# epiano.net
KiCad netlist of a schematic drawn in EAGLE
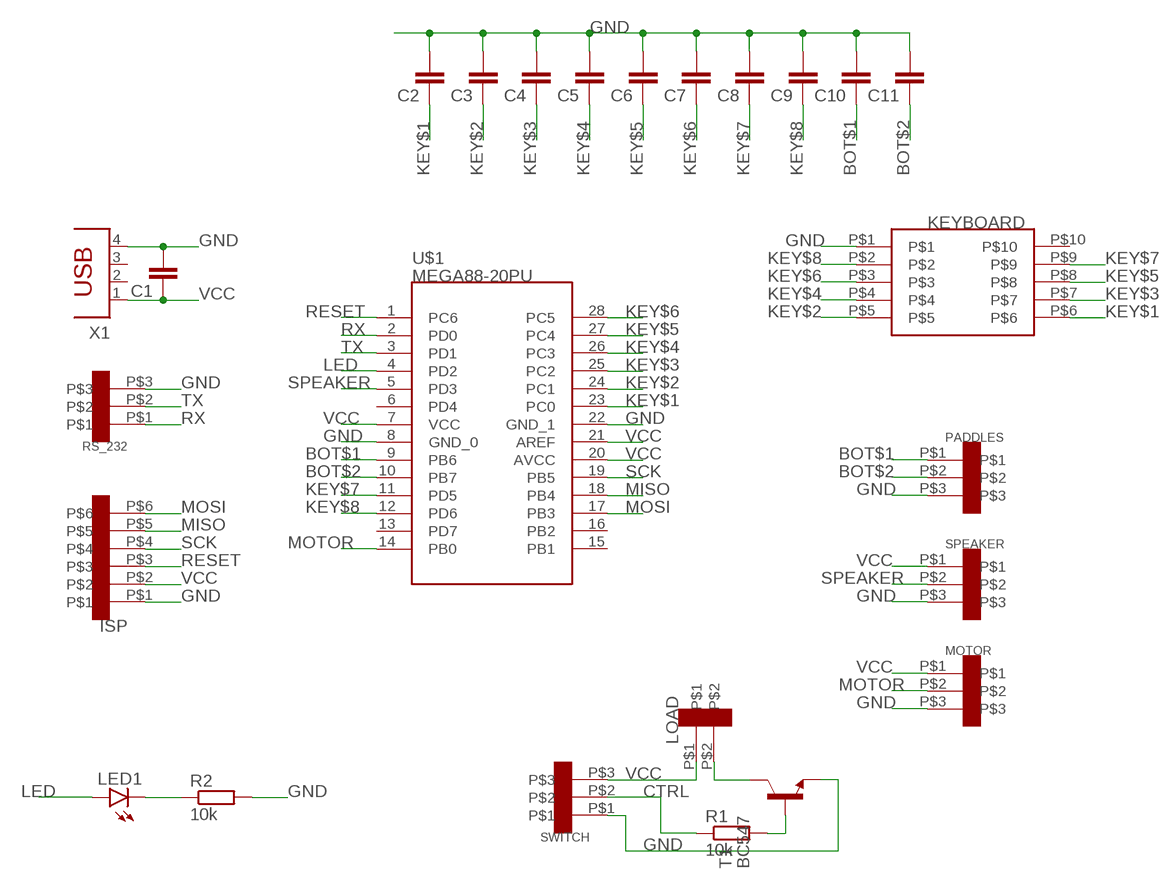
[diagram p0: schematic, sheet 1]

(export (version "E")
  (design (tool "Eeschema 10.0.6"))
  (components
    (comp (ref "C1")
      (value "C-EU025-060X050")
      (footprint "eagle-import:C025-060X050")
      (libsource (lib "eagle-import") (part "C-EU025-060X050"))
    )
    (comp (ref "C2")
      (value "C-EU025-024X044")
      (footprint "eagle-import:C025-024X044")
      (libsource (lib "eagle-import") (part "C-EU025-024X044"))
    )
    (comp (ref "C3")
      (value "C-EU025-024X044")
      (footprint "eagle-import:C025-024X044")
      (libsource (lib "eagle-import") (part "C-EU025-024X044"))
    )
    (comp (ref "C4")
      (value "C-EU025-024X044")
      (footprint "eagle-import:C025-024X044")
      (libsource (lib "eagle-import") (part "C-EU025-024X044"))
    )
    (comp (ref "C5")
      (value "C-EU025-024X044")
      (footprint "eagle-import:C025-024X044")
      (libsource (lib "eagle-import") (part "C-EU025-024X044"))
    )
    (comp (ref "C6")
      (value "C-EU025-024X044")
      (footprint "eagle-import:C025-024X044")
      (libsource (lib "eagle-import") (part "C-EU025-024X044"))
    )
    (comp (ref "C7")
      (value "C-EU025-024X044")
      (footprint "eagle-import:C025-024X044")
      (libsource (lib "eagle-import") (part "C-EU025-024X044"))
    )
    (comp (ref "C8")
      (value "C-EU025-024X044")
      (footprint "eagle-import:C025-024X044")
      (libsource (lib "eagle-import") (part "C-EU025-024X044"))
    )
    (comp (ref "C9")
      (value "C-EU025-024X044")
      (footprint "eagle-import:C025-024X044")
      (libsource (lib "eagle-import") (part "C-EU025-024X044"))
    )
    (comp (ref "C10")
      (value "C-EU025-024X044")
      (footprint "eagle-import:C025-024X044")
      (libsource (lib "eagle-import") (part "C-EU025-024X044"))
    )
    (comp (ref "C11")
      (value "C-EU025-024X044")
      (footprint "eagle-import:C025-024X044")
      (libsource (lib "eagle-import") (part "C-EU025-024X044"))
    )
    (comp (ref "ISP")
      (value "CON_DIL_6")
      (footprint "eagle-import:CON_DIL_6")
      (libsource (lib "eagle-import") (part "CON_DIL_6"))
    )
    (comp (ref "KEYBOARD")
      (value "CON_DIL_2X5")
      (footprint "eagle-import:CON_DIL_2X5")
      (libsource (lib "eagle-import") (part "CON_DIL_2X5"))
    )
    (comp (ref "LED1")
      (value "LED3MM")
      (footprint "eagle-import:LED3MM")
      (libsource (lib "eagle-import") (part "LED3MM"))
    )
    (comp (ref "LOAD")
      (value "CON_DIL_2")
      (footprint "eagle-import:CON_DIL_2")
      (libsource (lib "eagle-import") (part "CON_DIL_2"))
    )
    (comp (ref "MOTOR")
      (value "CON_DIL_3")
      (footprint "eagle-import:CON_DIL_3")
      (libsource (lib "eagle-import") (part "CON_DIL_3"))
    )
    (comp (ref "PADDLES")
      (value "CON_DIL_3")
      (footprint "eagle-import:CON_DIL_3")
      (libsource (lib "eagle-import") (part "CON_DIL_3"))
    )
    (comp (ref "R1")
      (value "10k")
      (footprint "eagle-import:0204_5")
      (libsource (lib "eagle-import") (part "R-EU_0204/5"))
    )
    (comp (ref "R2")
      (value "10k")
      (footprint "eagle-import:0207_15")
      (libsource (lib "eagle-import") (part "R-EU_0207/15"))
    )
    (comp (ref "RS_232")
      (value "CON_DIL_3")
      (footprint "eagle-import:CON_DIL_3")
      (libsource (lib "eagle-import") (part "CON_DIL_3"))
    )
    (comp (ref "SPEAKER")
      (value "CON_DIL_3")
      (footprint "eagle-import:CON_DIL_3")
      (libsource (lib "eagle-import") (part "CON_DIL_3"))
    )
    (comp (ref "SWITCH")
      (value "CON_DIL_3")
      (footprint "eagle-import:CON_DIL_3")
      (libsource (lib "eagle-import") (part "CON_DIL_3"))
    )
    (comp (ref "T1")
      (value "BC547")
      (footprint "eagle-import:TO92")
      (libsource (lib "eagle-import") (part "BC547"))
    )
    (comp (ref "U$1")
      (value "MEGA88-20PU")
      (footprint "eagle-import:DIL28-3")
      (libsource (lib "eagle-import") (part "MEGA88-20PU"))
    )
    (comp (ref "X1")
      (value "PN87520")
      (footprint "eagle-import:PN87520")
      (libsource (lib "eagle-import") (part "PN87520"))
    )
  )
  (nets
    (net (code "1") (name "/BOT$1") (class "Default")
      (node (ref "C10") (pin "1") (pinfunction "1_1") (pintype "passive"))
      (node (ref "PADDLES") (pin "P$1") (pinfunction "P$1_P$1") (pintype "bidirectional"))
      (node (ref "U$1") (pin "9") (pinfunction "PB6_9") (pintype "bidirectional"))
    )
    (net (code "2") (name "/BOT$2") (class "Default")
      (node (ref "C11") (pin "1") (pinfunction "1_1") (pintype "passive"))
      (node (ref "PADDLES") (pin "P$2") (pinfunction "P$2_P$2") (pintype "bidirectional"))
      (node (ref "U$1") (pin "10") (pinfunction "PB7_10") (pintype "bidirectional"))
    )
    (net (code "3") (name "/CTRL") (class "Default")
      (node (ref "R1") (pin "1") (pinfunction "1_1") (pintype "passive"))
      (node (ref "SWITCH") (pin "P$2") (pinfunction "P$2_P$2") (pintype "bidirectional"))
    )
    (net (code "4") (name "/GND") (class "Default")
      (node (ref "C1") (pin "2") (pinfunction "2_2") (pintype "passive"))
      (node (ref "C10") (pin "2") (pinfunction "2_2") (pintype "passive"))
      (node (ref "C11") (pin "2") (pinfunction "2_2") (pintype "passive"))
      (node (ref "C2") (pin "2") (pinfunction "2_2") (pintype "passive"))
      (node (ref "C3") (pin "2") (pinfunction "2_2") (pintype "passive"))
      (node (ref "C4") (pin "2") (pinfunction "2_2") (pintype "passive"))
      (node (ref "C5") (pin "2") (pinfunction "2_2") (pintype "passive"))
      (node (ref "C6") (pin "2") (pinfunction "2_2") (pintype "passive"))
      (node (ref "C7") (pin "2") (pinfunction "2_2") (pintype "passive"))
      (node (ref "C8") (pin "2") (pinfunction "2_2") (pintype "passive"))
      (node (ref "C9") (pin "2") (pinfunction "2_2") (pintype "passive"))
      (node (ref "ISP") (pin "P$1") (pinfunction "P$1_P$1") (pintype "bidirectional"))
      (node (ref "KEYBOARD") (pin "P$1") (pinfunction "P$1_P$1") (pintype "bidirectional"))
      (node (ref "MOTOR") (pin "P$3") (pinfunction "P$3_P$3") (pintype "bidirectional"))
      (node (ref "PADDLES") (pin "P$3") (pinfunction "P$3_P$3") (pintype "bidirectional"))
      (node (ref "R2") (pin "2") (pinfunction "2_2") (pintype "passive"))
      (node (ref "RS_232") (pin "P$3") (pinfunction "P$3_P$3") (pintype "bidirectional"))
      (node (ref "SPEAKER") (pin "P$3") (pinfunction "P$3_P$3") (pintype "bidirectional"))
      (node (ref "SWITCH") (pin "P$1") (pinfunction "P$1_P$1") (pintype "bidirectional"))
      (node (ref "T1") (pin "1") (pinfunction "E_1") (pintype "passive"))
      (node (ref "U$1") (pin "22") (pinfunction "GND_1_22") (pintype "bidirectional"))
      (node (ref "U$1") (pin "8") (pinfunction "GND_0_8") (pintype "bidirectional"))
      (node (ref "X1") (pin "4") (pinfunction "4_4") (pintype "passive"))
    )
    (net (code "5") (name "/KEY$1") (class "Default")
      (node (ref "C2") (pin "1") (pinfunction "1_1") (pintype "passive"))
      (node (ref "KEYBOARD") (pin "P$6") (pinfunction "P$6_P$6") (pintype "bidirectional"))
      (node (ref "U$1") (pin "23") (pinfunction "PC0_23") (pintype "bidirectional"))
    )
    (net (code "6") (name "/KEY$2") (class "Default")
      (node (ref "C3") (pin "1") (pinfunction "1_1") (pintype "passive"))
      (node (ref "KEYBOARD") (pin "P$5") (pinfunction "P$5_P$5") (pintype "bidirectional"))
      (node (ref "U$1") (pin "24") (pinfunction "PC1_24") (pintype "bidirectional"))
    )
    (net (code "7") (name "/KEY$3") (class "Default")
      (node (ref "C4") (pin "1") (pinfunction "1_1") (pintype "passive"))
      (node (ref "KEYBOARD") (pin "P$7") (pinfunction "P$7_P$7") (pintype "bidirectional"))
      (node (ref "U$1") (pin "25") (pinfunction "PC2_25") (pintype "bidirectional"))
    )
    (net (code "8") (name "/KEY$4") (class "Default")
      (node (ref "C5") (pin "1") (pinfunction "1_1") (pintype "passive"))
      (node (ref "KEYBOARD") (pin "P$4") (pinfunction "P$4_P$4") (pintype "bidirectional"))
      (node (ref "U$1") (pin "26") (pinfunction "PC3_26") (pintype "bidirectional"))
    )
    (net (code "9") (name "/KEY$5") (class "Default")
      (node (ref "C6") (pin "1") (pinfunction "1_1") (pintype "passive"))
      (node (ref "KEYBOARD") (pin "P$8") (pinfunction "P$8_P$8") (pintype "bidirectional"))
      (node (ref "U$1") (pin "27") (pinfunction "PC4_27") (pintype "bidirectional"))
    )
    (net (code "10") (name "/KEY$6") (class "Default")
      (node (ref "C7") (pin "1") (pinfunction "1_1") (pintype "passive"))
      (node (ref "KEYBOARD") (pin "P$3") (pinfunction "P$3_P$3") (pintype "bidirectional"))
      (node (ref "U$1") (pin "28") (pinfunction "PC5_28") (pintype "bidirectional"))
    )
    (net (code "11") (name "/KEY$7") (class "Default")
      (node (ref "C8") (pin "1") (pinfunction "1_1") (pintype "passive"))
      (node (ref "KEYBOARD") (pin "P$9") (pinfunction "P$9_P$9") (pintype "bidirectional"))
      (node (ref "U$1") (pin "11") (pinfunction "PD5_11") (pintype "bidirectional"))
    )
    (net (code "12") (name "/KEY$8") (class "Default")
      (node (ref "C9") (pin "1") (pinfunction "1_1") (pintype "passive"))
      (node (ref "KEYBOARD") (pin "P$2") (pinfunction "P$2_P$2") (pintype "bidirectional"))
      (node (ref "U$1") (pin "12") (pinfunction "PD6_12") (pintype "bidirectional"))
    )
    (net (code "13") (name "/LED") (class "Default")
      (node (ref "LED1") (pin "A") (pinfunction "A_A") (pintype "passive"))
      (node (ref "U$1") (pin "4") (pinfunction "PD2_4") (pintype "bidirectional"))
    )
    (net (code "14") (name "/MISO") (class "Default")
      (node (ref "ISP") (pin "P$5") (pinfunction "P$5_P$5") (pintype "bidirectional"))
      (node (ref "U$1") (pin "18") (pinfunction "PB4_18") (pintype "bidirectional"))
    )
    (net (code "15") (name "/MOSI") (class "Default")
      (node (ref "ISP") (pin "P$6") (pinfunction "P$6_P$6") (pintype "bidirectional"))
      (node (ref "U$1") (pin "17") (pinfunction "PB3_17") (pintype "bidirectional"))
    )
    (net (code "16") (name "/MOTOR") (class "Default")
      (node (ref "MOTOR") (pin "P$2") (pinfunction "P$2_P$2") (pintype "bidirectional"))
      (node (ref "U$1") (pin "14") (pinfunction "PB0_14") (pintype "bidirectional"))
    )
    (net (code "17") (name "/RESET") (class "Default")
      (node (ref "ISP") (pin "P$3") (pinfunction "P$3_P$3") (pintype "bidirectional"))
      (node (ref "U$1") (pin "1") (pinfunction "PC6_1") (pintype "bidirectional"))
    )
    (net (code "18") (name "/RX") (class "Default")
      (node (ref "RS_232") (pin "P$1") (pinfunction "P$1_P$1") (pintype "bidirectional"))
      (node (ref "U$1") (pin "2") (pinfunction "PD0_2") (pintype "bidirectional"))
    )
    (net (code "19") (name "/SCK") (class "Default")
      (node (ref "ISP") (pin "P$4") (pinfunction "P$4_P$4") (pintype "bidirectional"))
      (node (ref "U$1") (pin "19") (pinfunction "PB5_19") (pintype "bidirectional"))
    )
    (net (code "20") (name "/SPEAKER") (class "Default")
      (node (ref "SPEAKER") (pin "P$2") (pinfunction "P$2_P$2") (pintype "bidirectional"))
      (node (ref "U$1") (pin "5") (pinfunction "PD3_5") (pintype "bidirectional"))
    )
    (net (code "21") (name "/TX") (class "Default")
      (node (ref "RS_232") (pin "P$2") (pinfunction "P$2_P$2") (pintype "bidirectional"))
      (node (ref "U$1") (pin "3") (pinfunction "PD1_3") (pintype "bidirectional"))
    )
    (net (code "22") (name "/VCC") (class "Default")
      (node (ref "C1") (pin "1") (pinfunction "1_1") (pintype "passive"))
      (node (ref "ISP") (pin "P$2") (pinfunction "P$2_P$2") (pintype "bidirectional"))
      (node (ref "LOAD") (pin "P$1") (pinfunction "P$1_P$1") (pintype "bidirectional"))
      (node (ref "MOTOR") (pin "P$1") (pinfunction "P$1_P$1") (pintype "bidirectional"))
      (node (ref "SPEAKER") (pin "P$1") (pinfunction "P$1_P$1") (pintype "bidirectional"))
      (node (ref "SWITCH") (pin "P$3") (pinfunction "P$3_P$3") (pintype "bidirectional"))
      (node (ref "U$1") (pin "20") (pinfunction "AVCC_20") (pintype "bidirectional"))
      (node (ref "U$1") (pin "21") (pinfunction "AREF_21") (pintype "bidirectional"))
      (node (ref "U$1") (pin "7") (pinfunction "VCC_7") (pintype "bidirectional"))
      (node (ref "X1") (pin "1") (pinfunction "1_1") (pintype "passive"))
    )
    (net (code "23") (name "Net-(LED1-C)") (class "Default")
      (node (ref "LED1") (pin "K") (pinfunction "C_K") (pintype "passive"))
      (node (ref "R2") (pin "1") (pinfunction "1_1") (pintype "passive"))
    )
    (net (code "24") (name "Net-(T1-B)") (class "Default")
      (node (ref "R1") (pin "2") (pinfunction "2_2") (pintype "passive"))
      (node (ref "T1") (pin "2") (pinfunction "B_2") (pintype "passive"))
    )
    (net (code "25") (name "Net-(T1-C)") (class "Default")
      (node (ref "LOAD") (pin "P$2") (pinfunction "P$2_P$2") (pintype "bidirectional"))
      (node (ref "T1") (pin "3") (pinfunction "C_3") (pintype "passive"))
    )
    (net (code "26") (name "unconnected-(KEYBOARD-PadP$10)") (class "Default")
      (node (ref "KEYBOARD") (pin "P$10") (pinfunction "P$10_P$10") (pintype "bidirectional"))
    )
    (net (code "27") (name "unconnected-(U$1-PB1-Pad15)") (class "Default")
      (node (ref "U$1") (pin "15") (pinfunction "PB1_15") (pintype "bidirectional"))
    )
    (net (code "28") (name "unconnected-(U$1-PB2-Pad16)") (class "Default")
      (node (ref "U$1") (pin "16") (pinfunction "PB2_16") (pintype "bidirectional"))
    )
    (net (code "29") (name "unconnected-(U$1-PD4-Pad6)") (class "Default")
      (node (ref "U$1") (pin "6") (pinfunction "PD4_6") (pintype "bidirectional"))
    )
    (net (code "30") (name "unconnected-(U$1-PD7-Pad13)") (class "Default")
      (node (ref "U$1") (pin "13") (pinfunction "PD7_13") (pintype "bidirectional"))
    )
    (net (code "31") (name "unconnected-(X1-Pad2)") (class "Default")
      (node (ref "X1") (pin "2") (pinfunction "2_2") (pintype "passive"))
    )
    (net (code "32") (name "unconnected-(X1-Pad3)") (class "Default")
      (node (ref "X1") (pin "3") (pinfunction "3_3") (pintype "passive"))
    )
  )
)
